# ESP_Testing_Adapter.net
KiCad netlist of a schematic drawn in EAGLE
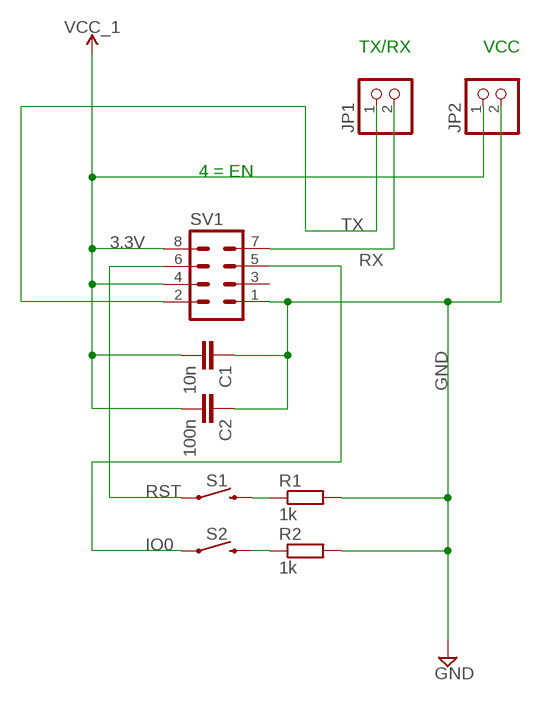
[diagram p0: schematic, sheet 1]

(export (version "E")
  (design (tool "Eeschema 10.0.6"))
  (components
    (comp (ref "C1")
      (value "10n")
      (footprint "eagle-import:C2.5-4")
      (libsource (lib "eagle-import") (part "C2.5/4"))
    )
    (comp (ref "C2")
      (value "100n")
      (footprint "eagle-import:C2.5-4")
      (libsource (lib "eagle-import") (part "C2.5/4"))
    )
    (comp (ref "JP1")
      (value "PINHD-1X2")
      (footprint "eagle-import:1X02")
      (libsource (lib "eagle-import") (part "PINHD-1X2"))
    )
    (comp (ref "JP2")
      (value "PINHD-1X2")
      (footprint "eagle-import:1X02")
      (libsource (lib "eagle-import") (part "PINHD-1X2"))
    )
    (comp (ref "R1")
      (value "1k")
      (footprint "eagle-import:0207_7")
      (libsource (lib "eagle-import") (part "R-EU_0207/7"))
    )
    (comp (ref "R2")
      (value "1k")
      (footprint "eagle-import:0207_7")
      (libsource (lib "eagle-import") (part "R-EU_0207/7"))
    )
    (comp (ref "S1")
      (value "MOMENTARY-SWITCH-SPST-PTH-6.0MM")
      (footprint "eagle-import:TACTILE_SWITCH_PTH_6.0MM")
      (libsource (lib "eagle-import") (part "MOMENTARY-SWITCH-SPST-PTH-6.0MM"))
    )
    (comp (ref "S2")
      (value "MOMENTARY-SWITCH-SPST-PTH-6.0MM")
      (footprint "eagle-import:TACTILE_SWITCH_PTH_6.0MM")
      (libsource (lib "eagle-import") (part "MOMENTARY-SWITCH-SPST-PTH-6.0MM"))
    )
    (comp (ref "SV1")
      (value "MA04-2")
      (footprint "eagle-import:MA04-2")
      (libsource (lib "eagle-import") (part "MA04-2"))
    )
  )
  (nets
    (net (code "1") (name "/IO0") (class "Default")
      (node (ref "S2") (pin "1") (pinfunction "1_1") (pintype "passive"))
      (node (ref "SV1") (pin "5") (pinfunction "5_5") (pintype "passive"))
    )
    (net (code "2") (name "/RST") (class "Default")
      (node (ref "S1") (pin "1") (pinfunction "1_1") (pintype "passive"))
      (node (ref "SV1") (pin "6") (pinfunction "6_6") (pintype "passive"))
    )
    (net (code "3") (name "/RX") (class "Default")
      (node (ref "JP1") (pin "2") (pinfunction "2_2") (pintype "passive"))
      (node (ref "SV1") (pin "7") (pinfunction "7_7") (pintype "passive"))
    )
    (net (code "4") (name "/TX") (class "Default")
      (node (ref "JP1") (pin "1") (pinfunction "1_1") (pintype "passive"))
      (node (ref "SV1") (pin "2") (pinfunction "2_2") (pintype "passive"))
    )
    (net (code "5") (name "GND") (class "Default")
      (node (ref "C1") (pin "1") (pinfunction "1_1") (pintype "passive"))
      (node (ref "C2") (pin "1") (pinfunction "1_1") (pintype "passive"))
      (node (ref "JP2") (pin "2") (pinfunction "2_2") (pintype "passive"))
      (node (ref "R1") (pin "2") (pinfunction "2_2") (pintype "passive"))
      (node (ref "R2") (pin "2") (pinfunction "2_2") (pintype "passive"))
      (node (ref "SV1") (pin "1") (pinfunction "1_1") (pintype "passive"))
    )
    (net (code "6") (name "Net-(S1-2)") (class "Default")
      (node (ref "R1") (pin "1") (pinfunction "1_1") (pintype "passive"))
      (node (ref "S1") (pin "3") (pinfunction "2_3") (pintype "passive"))
    )
    (net (code "7") (name "Net-(S2-2)") (class "Default")
      (node (ref "R2") (pin "1") (pinfunction "1_1") (pintype "passive"))
      (node (ref "S2") (pin "3") (pinfunction "2_3") (pintype "passive"))
    )
    (net (code "8") (name "VCC_1") (class "Default")
      (node (ref "C1") (pin "2") (pinfunction "2_2") (pintype "passive"))
      (node (ref "C2") (pin "2") (pinfunction "2_2") (pintype "passive"))
      (node (ref "JP2") (pin "1") (pinfunction "1_1") (pintype "passive"))
      (node (ref "SV1") (pin "4") (pinfunction "4_4") (pintype "passive"))
      (node (ref "SV1") (pin "8") (pinfunction "8_8") (pintype "passive"))
    )
    (net (code "9") (name "unconnected-(SV1-Pad3)") (class "Default")
      (node (ref "SV1") (pin "3") (pinfunction "3_3") (pintype "passive"))
    )
  )
)
